# Back.net
KiCad netlist of a schematic drawn in Altium Designer
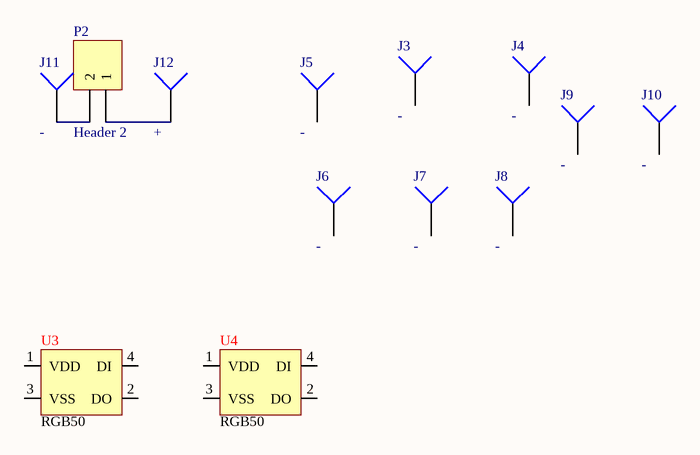
[diagram p0: Back.SchDoc]

(export (version "E")
  (design (tool "Eeschema 10.0.6"))
  (components
    (comp (ref "J3")
      (value "-")
      (footprint "Padl")
      (description "Socket")
      (fields (field (name "PUBLISHER") "Altium Limited"))
      (libsource (lib "Miscellaneous Connectors") (part "Socket"))
    )
    (comp (ref "J4")
      (value "-")
      (footprint "Padl")
      (description "Socket")
      (fields (field (name "PUBLISHER") "Altium Limited"))
      (libsource (lib "Miscellaneous Connectors") (part "Socket"))
    )
    (comp (ref "J5")
      (value "-")
      (footprint "Padl")
      (description "Socket")
      (fields (field (name "PUBLISHER") "Altium Limited"))
      (libsource (lib "Miscellaneous Connectors") (part "Socket"))
    )
    (comp (ref "J6")
      (value "-")
      (footprint "Padl")
      (description "Socket")
      (fields (field (name "PUBLISHER") "Altium Limited"))
      (libsource (lib "Miscellaneous Connectors") (part "Socket"))
    )
    (comp (ref "J7")
      (value "-")
      (footprint "Padl")
      (description "Socket")
      (fields (field (name "PUBLISHER") "Altium Limited"))
      (libsource (lib "Miscellaneous Connectors") (part "Socket"))
    )
    (comp (ref "J8")
      (value "-")
      (footprint "Padl")
      (description "Socket")
      (fields (field (name "PUBLISHER") "Altium Limited"))
      (libsource (lib "Miscellaneous Connectors") (part "Socket"))
    )
    (comp (ref "J9")
      (value "-")
      (footprint "Padl")
      (description "Socket")
      (fields (field (name "PUBLISHER") "Altium Limited"))
      (libsource (lib "Miscellaneous Connectors") (part "Socket"))
    )
    (comp (ref "J10")
      (value "-")
      (footprint "Padl")
      (description "Socket")
      (fields (field (name "PUBLISHER") "Altium Limited"))
      (libsource (lib "Miscellaneous Connectors") (part "Socket"))
    )
    (comp (ref "J11")
      (value "-")
      (footprint "PIN")
      (description "Socket")
      (fields (field (name "PUBLISHER") "Altium Limited"))
      (libsource (lib "Miscellaneous Connectors") (part "Socket"))
    )
    (comp (ref "J12")
      (value "+")
      (footprint "PIN")
      (description "Socket")
      (fields (field (name "PUBLISHER") "Altium Limited"))
      (libsource (lib "Miscellaneous Connectors") (part "Socket"))
    )
    (comp (ref "P2")
      (value "Header 2")
      (footprint "HEAD2.0")
      (description "电池供电跳线帽")
      (fields (field (name "PUBLISHER") "Altium Limited"))
      (libsource (lib "Miscellaneous Connectors") (part "Header 2"))
    )
    (comp (ref "U3")
      (value "RGB50")
      (footprint "EYE-BLOCK")
      (libsource (lib "甲壳虫Geek-InSect") (part "RGB50"))
    )
    (comp (ref "U4")
      (value "RGB50")
      (footprint "EYE-BLOCK")
      (libsource (lib "甲壳虫Geek-InSect") (part "RGB50"))
    )
  )
  (nets
    (net (code "1") (name "Net-(J11-Pad1)") (class "Default")
      (node (ref "J11") (pin "1") (pinfunction "1_1") (pintype "passive"))
      (node (ref "P2") (pin "2") (pinfunction "2_2") (pintype "passive"))
    )
    (net (code "2") (name "Net-(J12-Pad1)") (class "Default")
      (node (ref "J12") (pin "1") (pinfunction "1_1") (pintype "passive"))
      (node (ref "P2") (pin "1") (pinfunction "1_1") (pintype "passive"))
    )
    (net (code "3") (name "unconnected-(J3-Pad1)") (class "Default")
      (node (ref "J3") (pin "1") (pinfunction "1_1") (pintype "passive"))
    )
    (net (code "4") (name "unconnected-(J4-Pad1)") (class "Default")
      (node (ref "J4") (pin "1") (pinfunction "1_1") (pintype "passive"))
    )
    (net (code "5") (name "unconnected-(J5-Pad1)") (class "Default")
      (node (ref "J5") (pin "1") (pinfunction "1_1") (pintype "passive"))
    )
    (net (code "6") (name "unconnected-(J6-Pad1)") (class "Default")
      (node (ref "J6") (pin "1") (pinfunction "1_1") (pintype "passive"))
    )
    (net (code "7") (name "unconnected-(J7-Pad1)") (class "Default")
      (node (ref "J7") (pin "1") (pinfunction "1_1") (pintype "passive"))
    )
    (net (code "8") (name "unconnected-(J8-Pad1)") (class "Default")
      (node (ref "J8") (pin "1") (pinfunction "1_1") (pintype "passive"))
    )
    (net (code "9") (name "unconnected-(J9-Pad1)") (class "Default")
      (node (ref "J9") (pin "1") (pinfunction "1_1") (pintype "passive"))
    )
    (net (code "10") (name "unconnected-(J10-Pad1)") (class "Default")
      (node (ref "J10") (pin "1") (pinfunction "1_1") (pintype "passive"))
    )
    (net (code "11") (name "unconnected-(U3-DI-Pad4)") (class "Default")
      (node (ref "U3") (pin "4") (pinfunction "DI_4") (pintype "passive"))
    )
    (net (code "12") (name "unconnected-(U3-DO-Pad2)") (class "Default")
      (node (ref "U3") (pin "2") (pinfunction "DO_2") (pintype "passive"))
    )
    (net (code "13") (name "unconnected-(U3-VDD-Pad1)") (class "Default")
      (node (ref "U3") (pin "1") (pinfunction "VDD_1") (pintype "passive"))
    )
    (net (code "14") (name "unconnected-(U3-VSS-Pad3)") (class "Default")
      (node (ref "U3") (pin "3") (pinfunction "VSS_3") (pintype "passive"))
    )
    (net (code "15") (name "unconnected-(U4-DI-Pad4)") (class "Default")
      (node (ref "U4") (pin "4") (pinfunction "DI_4") (pintype "passive"))
    )
    (net (code "16") (name "unconnected-(U4-DO-Pad2)") (class "Default")
      (node (ref "U4") (pin "2") (pinfunction "DO_2") (pintype "passive"))
    )
    (net (code "17") (name "unconnected-(U4-VDD-Pad1)") (class "Default")
      (node (ref "U4") (pin "1") (pinfunction "VDD_1") (pintype "passive"))
    )
    (net (code "18") (name "unconnected-(U4-VSS-Pad3)") (class "Default")
      (node (ref "U4") (pin "3") (pinfunction "VSS_3") (pintype "passive"))
    )
  )
)
